# L298.net
KiCad netlist of a schematic drawn in Altium Designer
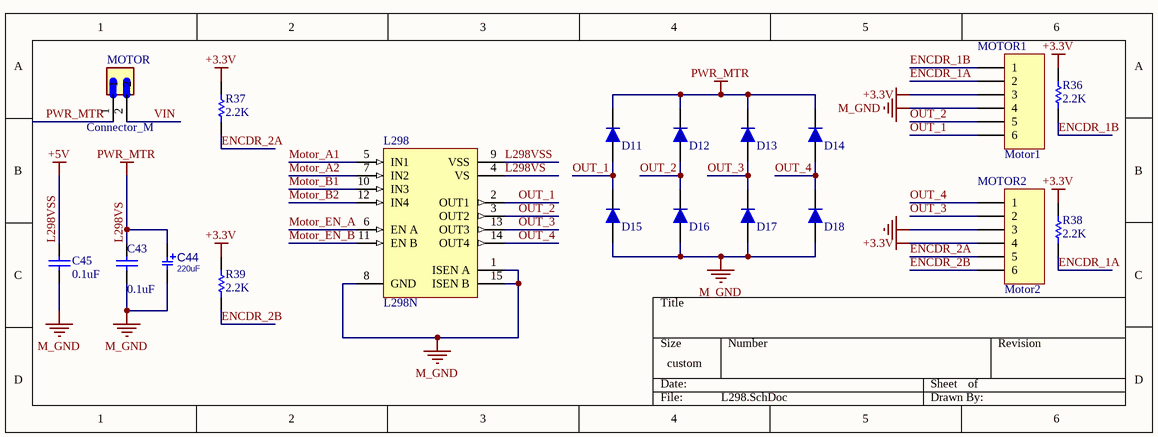
[diagram p0: L298.SchDoc]

(export (version "E")
  (design (tool "Eeschema 10.0.6"))
  (components
    (comp (ref "C43")
      (value "0.1uF")
      (footprint "CAPC3413X12N")
      (description "CAP 0805")
      (fields (field (name "DESIGNER") "Abbas Basereh"))
      (libsource (lib "Altium") (part "CAP SMD 0805"))
    )
    (comp (ref "C44")
      (value "220uF")
      (footprint "C_EL_6_6")
      (description "CAP, THD, ELEC,")
      (fields (field (name "MANF_P#") "MANF_PART#") (field (name "MANF") "MANF"))
      (libsource (lib "Passive") (part "CAP_SMD_EL"))
    )
    (comp (ref "C45")
      (value "0.1uF")
      (footprint "CAPC3413X12N")
      (description "CAP 0805")
      (fields (field (name "DESIGNER") "Abbas Basereh"))
      (libsource (lib "Altium") (part "CAP SMD 0805"))
    )
    (comp (ref "D11")
      (value "1n4007")
      (footprint "DIOM4629X24N")
      (description "Standard Rectifiers")
      (fields (field (name "MANUFACTURER") "DC COMPONENTS") (field (name "DESIGNER") "Abbas Basereh"))
      (libsource (lib "Altium") (part "1n4007 SMD M7"))
    )
    (comp (ref "D12")
      (value "1n4007")
      (footprint "DIOM4629X24N")
      (description "Standard Rectifiers")
      (fields (field (name "MANUFACTURER") "DC COMPONENTS") (field (name "DESIGNER") "Abbas Basereh"))
      (libsource (lib "Altium") (part "1n4007 SMD M7"))
    )
    (comp (ref "D13")
      (value "1n4007")
      (footprint "DIOM4629X24N")
      (description "Standard Rectifiers")
      (fields (field (name "MANUFACTURER") "DC COMPONENTS") (field (name "DESIGNER") "Abbas Basereh"))
      (libsource (lib "Altium") (part "1n4007 SMD M7"))
    )
    (comp (ref "D14")
      (value "1n4007")
      (footprint "DIOM4629X24N")
      (description "Standard Rectifiers")
      (fields (field (name "MANUFACTURER") "DC COMPONENTS") (field (name "DESIGNER") "Abbas Basereh"))
      (libsource (lib "Altium") (part "1n4007 SMD M7"))
    )
    (comp (ref "D15")
      (value "1n4007")
      (footprint "DIOM4629X24N")
      (description "Standard Rectifiers")
      (fields (field (name "MANUFACTURER") "DC COMPONENTS") (field (name "DESIGNER") "Abbas Basereh"))
      (libsource (lib "Altium") (part "1n4007 SMD M7"))
    )
    (comp (ref "D16")
      (value "1n4007")
      (footprint "DIOM4629X24N")
      (description "Standard Rectifiers")
      (fields (field (name "MANUFACTURER") "DC COMPONENTS") (field (name "DESIGNER") "Abbas Basereh"))
      (libsource (lib "Altium") (part "1n4007 SMD M7"))
    )
    (comp (ref "D17")
      (value "1n4007")
      (footprint "DIOM4629X24N")
      (description "Standard Rectifiers")
      (fields (field (name "MANUFACTURER") "DC COMPONENTS") (field (name "DESIGNER") "Abbas Basereh"))
      (libsource (lib "Altium") (part "1n4007 SMD M7"))
    )
    (comp (ref "D18")
      (value "1n4007")
      (footprint "DIOM4629X24N")
      (description "Standard Rectifiers")
      (fields (field (name "MANUFACTURER") "DC COMPONENTS") (field (name "DESIGNER") "Abbas Basereh"))
      (libsource (lib "Altium") (part "1n4007 SMD M7"))
    )
    (comp (ref "L298")
      (value "L298N")
      (footprint "Multiwatt15H")
      (description "Dual Full Bridge Driver")
      (fields (field (name "PUBLISHER") "Altium Limited"))
      (libsource (lib "Altium") (part "L298N"))
    )
    (comp (ref "MOTOR")
      (value "Connector_M")
      (footprint "JST_B2P-VH(LF)(SN)")
      (description "Connector Header Through Hole 2 position 0.156 (3.96mm)")
      (fields (field (name "MP") "B2P-VH(LF)(SN)") (field (name "MF") "JST Sales"))
      (libsource (lib "B2P-VH_LF__SN_") (part "B2P-VH(LF)(SN)"))
    )
    (comp (ref "MOTOR1")
      (value "Motor1")
      (footprint "MO-Header 6")
      (description "Header, 6-Pin")
      (fields (field (name "PUBLISHER") "Altium Limited"))
      (libsource (lib "Altium") (part "Header 6"))
    )
    (comp (ref "MOTOR2")
      (value "Motor2")
      (footprint "MO-Header 6")
      (description "Header, 6-Pin")
      (fields (field (name "PUBLISHER") "Altium Limited"))
      (libsource (lib "Altium") (part "Header 6"))
    )
    (comp (ref "R36")
      (value "2.2K")
      (footprint "RESC3413X04N")
      (description "RES 0805")
      (fields (field (name "DESIGNER") "Abbas Basereh"))
      (libsource (lib "Altium") (part "RES 0805 0.125W"))
    )
    (comp (ref "R37")
      (value "2.2K")
      (footprint "RESC3413X04N")
      (description "RES 0805")
      (fields (field (name "DESIGNER") "Abbas Basereh"))
      (libsource (lib "Altium") (part "RES 0805 0.125W"))
    )
    (comp (ref "R38")
      (value "2.2K")
      (footprint "RESC3413X04N")
      (description "RES 0805")
      (fields (field (name "DESIGNER") "Abbas Basereh"))
      (libsource (lib "Altium") (part "RES 0805 0.125W"))
    )
    (comp (ref "R39")
      (value "2.2K")
      (footprint "RESC3413X04N")
      (description "RES 0805")
      (fields (field (name "DESIGNER") "Abbas Basereh"))
      (libsource (lib "Altium") (part "RES 0805 0.125W"))
    )
  )
  (nets
    (net (code "1") (name "+3.3V") (class "Default")
      (node (ref "MOTOR1") (pin "3") (pinfunction "3_3") (pintype "passive"))
      (node (ref "MOTOR2") (pin "4") (pinfunction "4_4") (pintype "passive"))
      (node (ref "R36") (pin "1") (pinfunction "1_1") (pintype "passive"))
      (node (ref "R37") (pin "1") (pinfunction "1_1") (pintype "passive"))
      (node (ref "R38") (pin "1") (pinfunction "1_1") (pintype "passive"))
      (node (ref "R39") (pin "1") (pinfunction "1_1") (pintype "passive"))
    )
    (net (code "2") (name "+5V") (class "Default")
      (node (ref "C45") (pin "2") (pinfunction "2_2") (pintype "passive"))
      (node (ref "L298") (pin "9") (pinfunction "VSS_9") (pintype "power_in"))
    )
    (net (code "3") (name "/ENCDR_1A") (class "Default")
      (node (ref "MOTOR1") (pin "2") (pinfunction "2_2") (pintype "passive"))
      (node (ref "R38") (pin "2") (pinfunction "2_2") (pintype "passive"))
    )
    (net (code "4") (name "/ENCDR_1B") (class "Default")
      (node (ref "MOTOR1") (pin "1") (pinfunction "1_1") (pintype "passive"))
      (node (ref "R36") (pin "2") (pinfunction "2_2") (pintype "passive"))
    )
    (net (code "5") (name "/ENCDR_2A") (class "Default")
      (node (ref "MOTOR2") (pin "5") (pinfunction "5_5") (pintype "passive"))
      (node (ref "R37") (pin "2") (pinfunction "2_2") (pintype "passive"))
    )
    (net (code "6") (name "/ENCDR_2B") (class "Default")
      (node (ref "MOTOR2") (pin "6") (pinfunction "6_6") (pintype "passive"))
      (node (ref "R39") (pin "2") (pinfunction "2_2") (pintype "passive"))
    )
    (net (code "7") (name "/Motor_A1") (class "Default")
      (node (ref "L298") (pin "5") (pinfunction "IN1_5") (pintype "input"))
    )
    (net (code "8") (name "/Motor_A2") (class "Default")
      (node (ref "L298") (pin "7") (pinfunction "IN2_7") (pintype "input"))
    )
    (net (code "9") (name "/Motor_B1") (class "Default")
      (node (ref "L298") (pin "10") (pinfunction "IN3_10") (pintype "input"))
    )
    (net (code "10") (name "/Motor_B2") (class "Default")
      (node (ref "L298") (pin "12") (pinfunction "IN4_12") (pintype "input"))
    )
    (net (code "11") (name "/Motor_EN_A") (class "Default")
      (node (ref "L298") (pin "6") (pinfunction "EN_A_6") (pintype "input"))
    )
    (net (code "12") (name "/Motor_EN_B") (class "Default")
      (node (ref "L298") (pin "11") (pinfunction "EN_B_11") (pintype "input"))
    )
    (net (code "13") (name "/OUT_1") (class "Default")
      (node (ref "D11") (pin "1") (pintype "passive"))
      (node (ref "D15") (pin "2") (pintype "passive"))
      (node (ref "L298") (pin "2") (pinfunction "OUT1_2") (pintype "output"))
      (node (ref "MOTOR1") (pin "6") (pinfunction "6_6") (pintype "passive"))
    )
    (net (code "14") (name "/OUT_2") (class "Default")
      (node (ref "D12") (pin "1") (pintype "passive"))
      (node (ref "D16") (pin "2") (pintype "passive"))
      (node (ref "L298") (pin "3") (pinfunction "OUT2_3") (pintype "output"))
      (node (ref "MOTOR1") (pin "5") (pinfunction "5_5") (pintype "passive"))
    )
    (net (code "15") (name "/OUT_3") (class "Default")
      (node (ref "D13") (pin "1") (pintype "passive"))
      (node (ref "D17") (pin "2") (pintype "passive"))
      (node (ref "L298") (pin "13") (pinfunction "OUT3_13") (pintype "output"))
      (node (ref "MOTOR2") (pin "2") (pinfunction "2_2") (pintype "passive"))
    )
    (net (code "16") (name "/OUT_4") (class "Default")
      (node (ref "D14") (pin "1") (pintype "passive"))
      (node (ref "D18") (pin "2") (pintype "passive"))
      (node (ref "L298") (pin "14") (pinfunction "OUT4_14") (pintype "output"))
      (node (ref "MOTOR2") (pin "1") (pinfunction "1_1") (pintype "passive"))
    )
    (net (code "17") (name "/VIN") (class "Default")
      (node (ref "MOTOR") (pin "2") (pinfunction "2_2") (pintype "passive"))
    )
    (net (code "18") (name "M_GND") (class "Default")
      (node (ref "C43") (pin "1") (pinfunction "1_1") (pintype "passive"))
      (node (ref "C44") (pin "2") (pinfunction "2_2") (pintype "passive"))
      (node (ref "C45") (pin "1") (pinfunction "1_1") (pintype "passive"))
      (node (ref "D15") (pin "1") (pintype "passive"))
      (node (ref "D16") (pin "1") (pintype "passive"))
      (node (ref "D17") (pin "1") (pintype "passive"))
      (node (ref "D18") (pin "1") (pintype "passive"))
      (node (ref "L298") (pin "1") (pinfunction "ISEN_A_1") (pintype "passive"))
      (node (ref "L298") (pin "15") (pinfunction "ISEN_B_15") (pintype "passive"))
      (node (ref "L298") (pin "8") (pinfunction "GND_8") (pintype "power_in"))
      (node (ref "MOTOR1") (pin "4") (pinfunction "4_4") (pintype "passive"))
      (node (ref "MOTOR2") (pin "3") (pinfunction "3_3") (pintype "passive"))
    )
    (net (code "19") (name "PWR_MTR") (class "Default")
      (node (ref "C43") (pin "2") (pinfunction "2_2") (pintype "passive"))
      (node (ref "C44") (pin "1") (pinfunction "1_1") (pintype "passive"))
      (node (ref "D11") (pin "2") (pintype "passive"))
      (node (ref "D12") (pin "2") (pintype "passive"))
      (node (ref "D13") (pin "2") (pintype "passive"))
      (node (ref "D14") (pin "2") (pintype "passive"))
      (node (ref "L298") (pin "4") (pinfunction "VS_4") (pintype "power_in"))
      (node (ref "MOTOR") (pin "1") (pinfunction "1_1") (pintype "passive"))
    )
  )
)
